# Solenoid_13.net
KiCad netlist of a schematic drawn in EAGLE
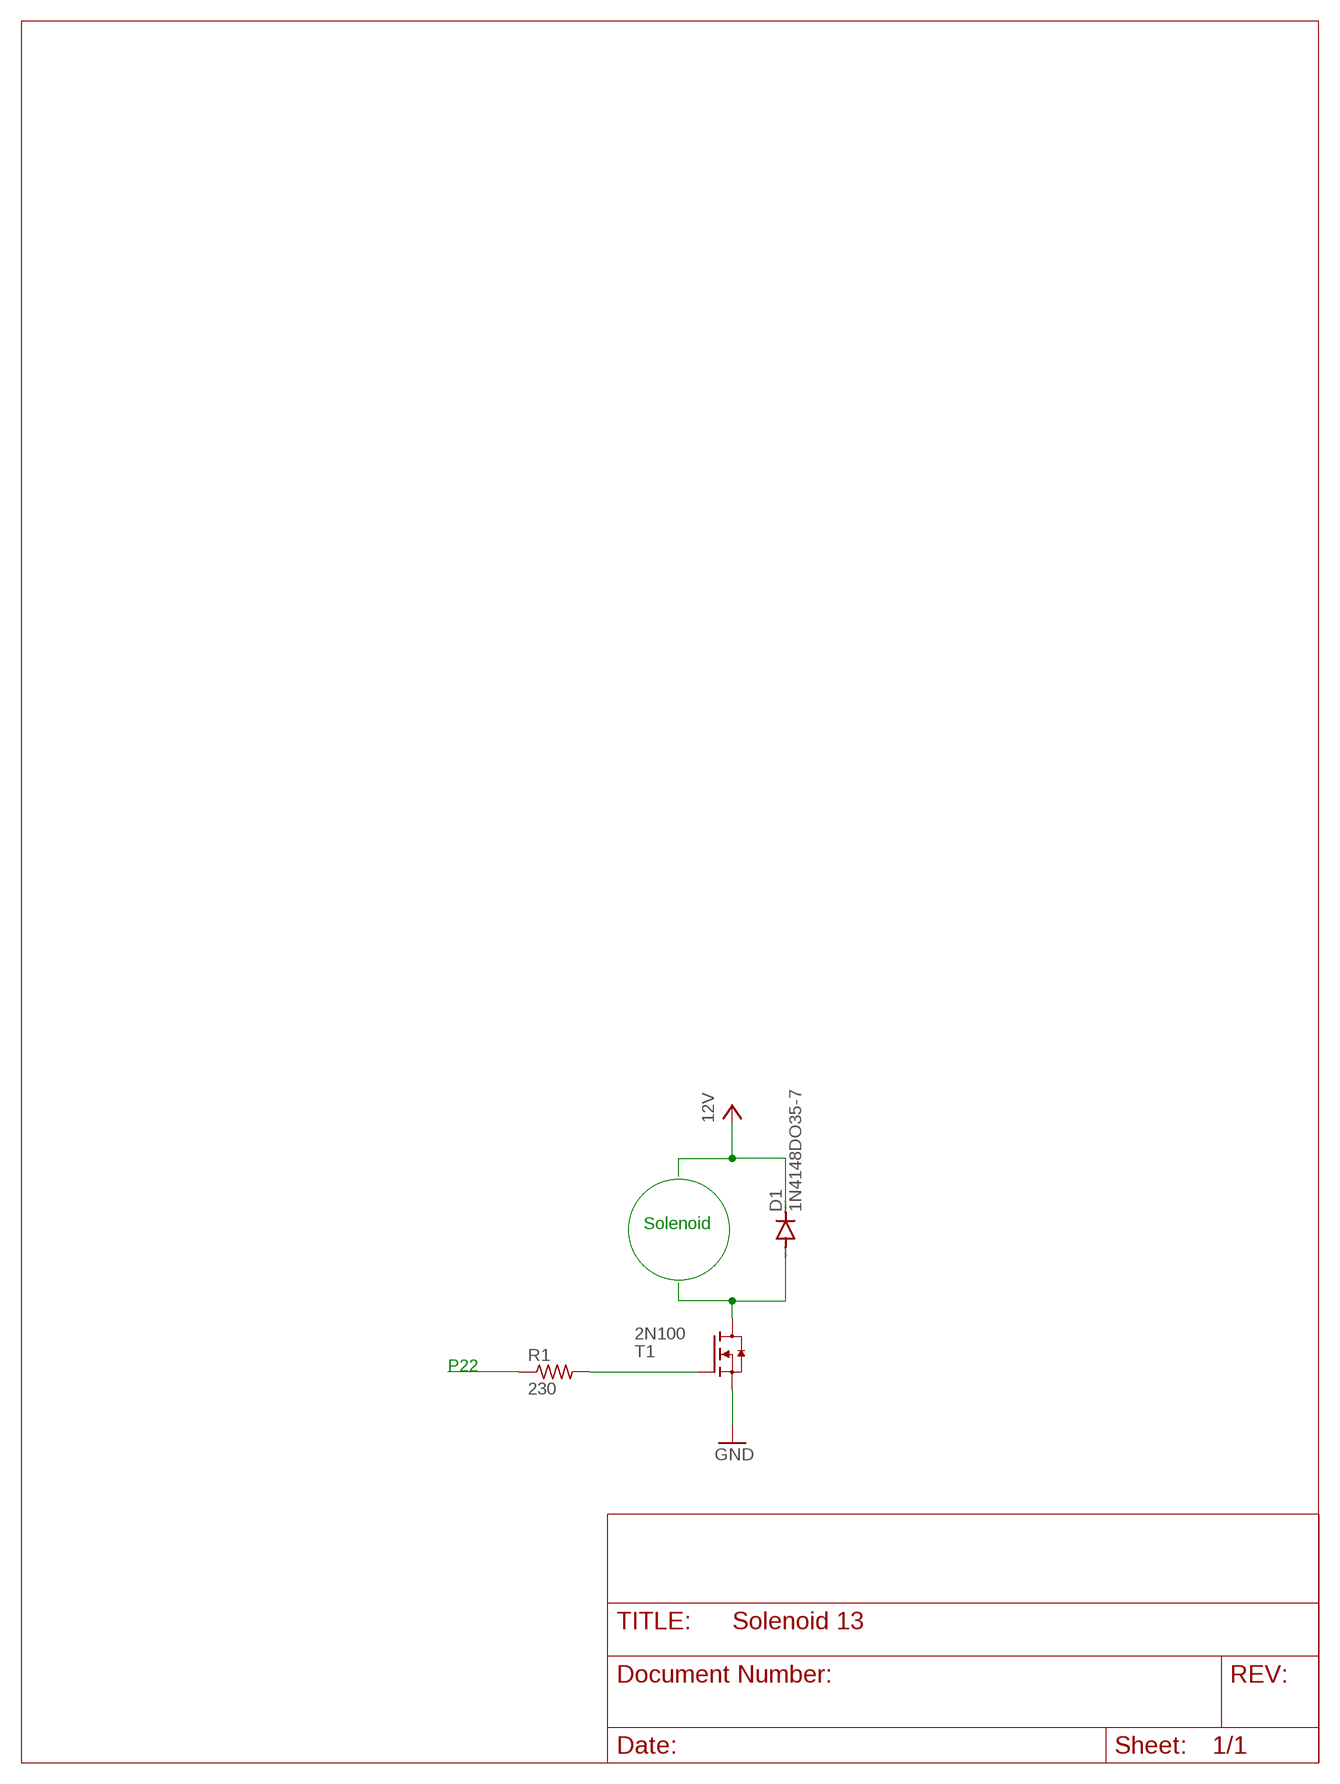
[diagram p0: schematic, sheet 1]

(export (version "E")
  (design (tool "Eeschema 10.0.6"))
  (components
    (comp (ref "D1")
      (value "1N4148DO35-7")
      (footprint "eagle-import:DO35-7")
      (libsource (lib "eagle-import") (part "1N4148DO35-7"))
    )
    (comp (ref "R1")
      (value "230")
      (footprint "eagle-import:0204_7")
      (libsource (lib "eagle-import") (part "R-US_0204/7"))
    )
    (comp (ref "T1")
      (value "2N100")
      (footprint "eagle-import:PG-TO263-7-3")
      (libsource (lib "eagle-import") (part "IPB180N06S4-H1"))
    )
  )
  (nets
    (net (code "1") (name "12V") (class "Default")
      (node (ref "D1") (pin "C") (pinfunction "C_C") (pintype "passive"))
    )
    (net (code "2") (name "GND") (class "Default")
      (node (ref "T1") (pin "2") (pinfunction "S_2") (pintype "passive"))
      (node (ref "T1") (pin "3") (pinfunction "S_3") (pintype "passive"))
      (node (ref "T1") (pin "5") (pinfunction "S_5") (pintype "passive"))
      (node (ref "T1") (pin "6") (pinfunction "S_6") (pintype "passive"))
      (node (ref "T1") (pin "7") (pinfunction "S_7") (pintype "passive"))
    )
    (net (code "3") (name "Net-(T1-D)") (class "Default")
      (node (ref "D1") (pin "A") (pinfunction "A_A") (pintype "passive"))
      (node (ref "T1") (pin "8") (pinfunction "D_8") (pintype "passive"))
    )
    (net (code "4") (name "Net-(T1-G)") (class "Default")
      (node (ref "R1") (pin "2") (pinfunction "2_2") (pintype "passive"))
      (node (ref "T1") (pin "1") (pinfunction "G_1") (pintype "passive"))
    )
    (net (code "5") (name "unconnected-(R1-Pad1)") (class "Default")
      (node (ref "R1") (pin "1") (pinfunction "1_1") (pintype "passive"))
    )
  )
)
